# SparkFun_6DoF_ISM330DHCX_Qwiic_Micro.net
KiCad netlist of a schematic drawn in EAGLE
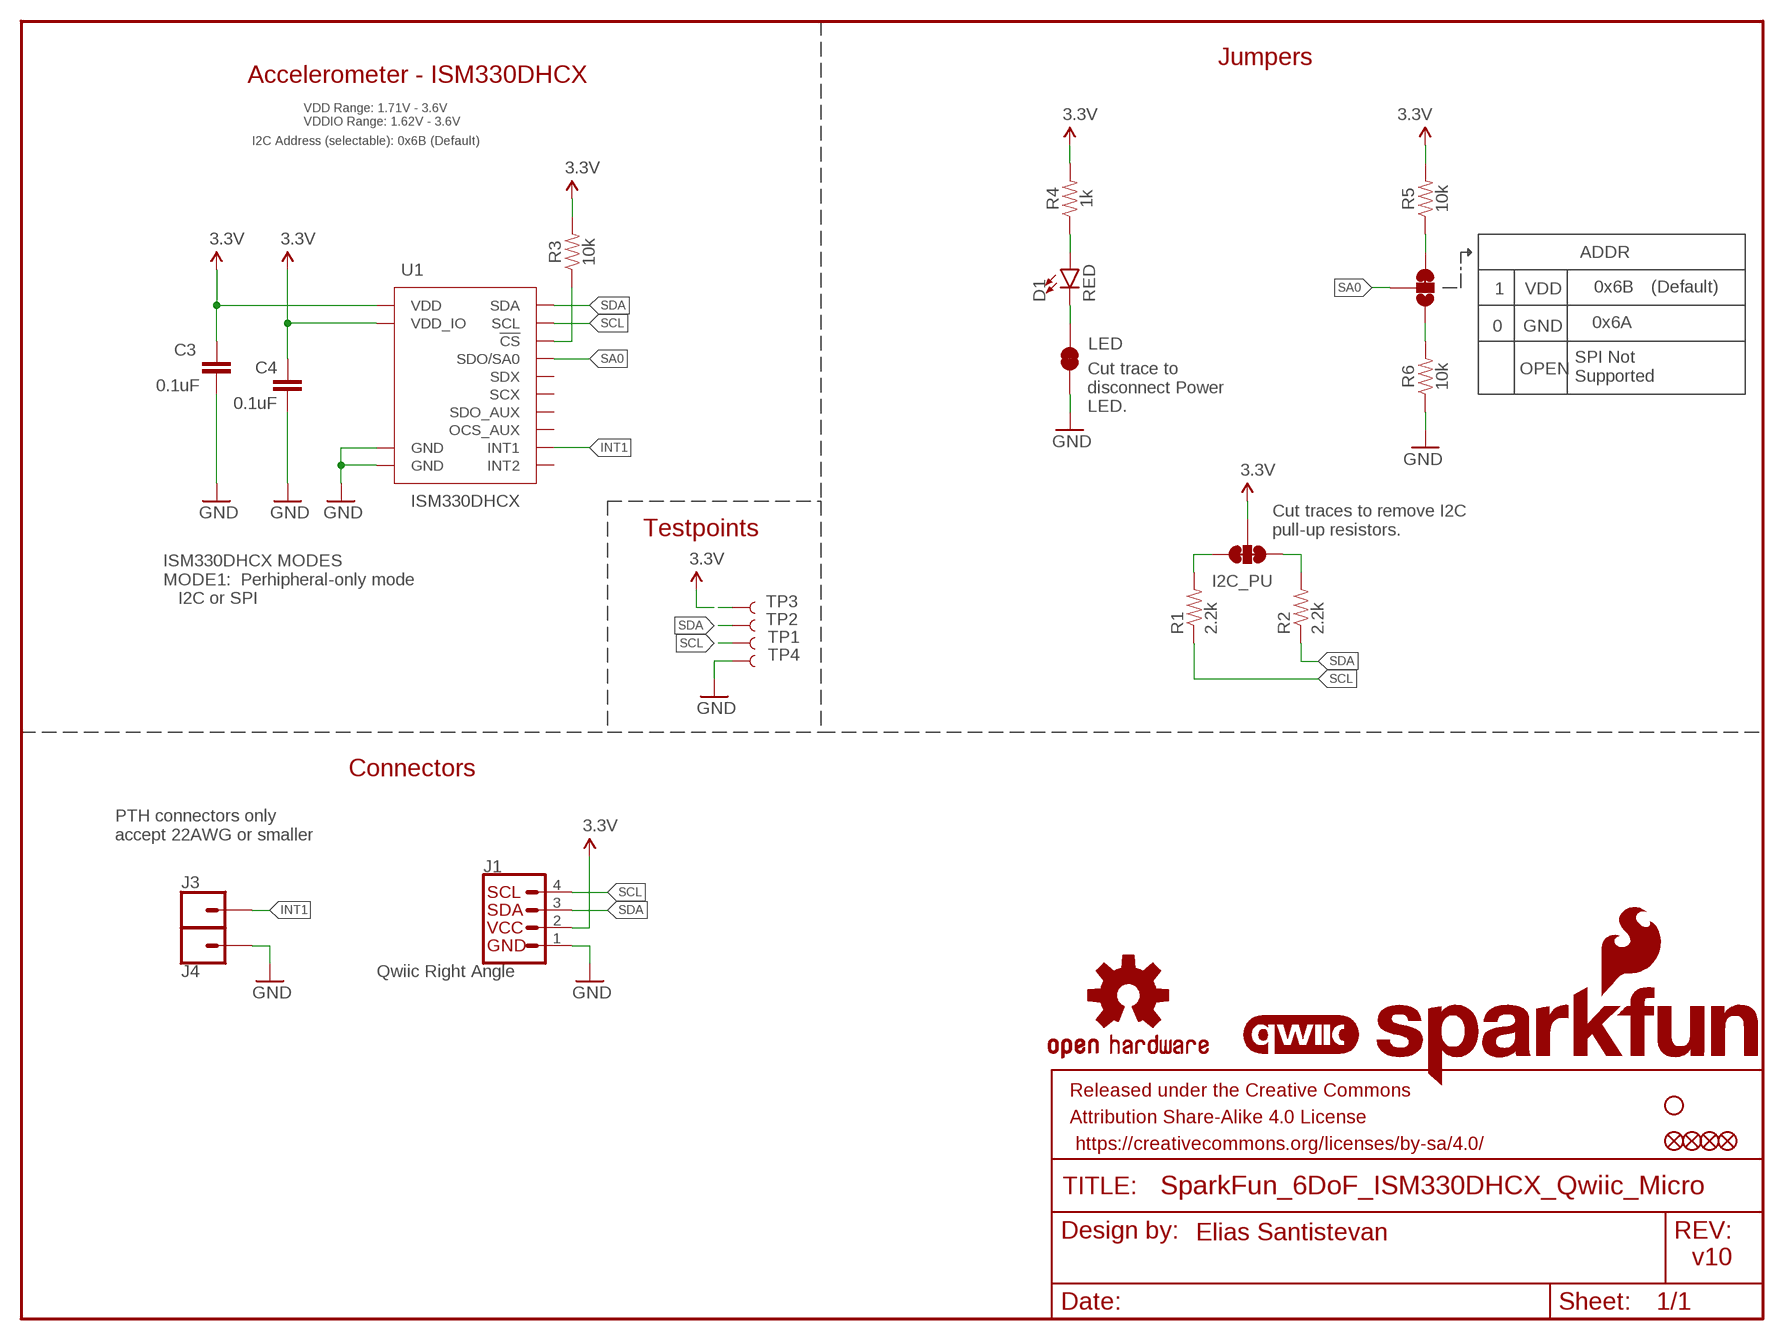
[diagram p0: schematic, sheet 1]

(export (version "E")
  (design (tool "Eeschema 10.0.6"))
  (components
    (comp (ref "ADDR")
      (value "JUMPER-SMT_3_1-NC_TRACE_SILK")
      (footprint "eagle-import:SMT-JUMPER_3_1-NC_TRACE_SILK")
      (libsource (lib "eagle-import") (part "JUMPER-SMT_3_1-NC_TRACE_SILK"))
    )
    (comp (ref "C3")
      (value "0.1uF")
      (footprint "eagle-import:0402-TIGHT")
      (libsource (lib "eagle-import") (part "0.1UF-0402T-6.3V-10%-X7R"))
    )
    (comp (ref "C4")
      (value "0.1uF")
      (footprint "eagle-import:0402-TIGHT")
      (libsource (lib "eagle-import") (part "0.1UF-0402T-6.3V-10%-X7R"))
    )
    (comp (ref "D1")
      (value "RED")
      (footprint "eagle-import:LED-0402")
      (libsource (lib "eagle-import") (part "LED-RED_0402"))
    )
    (comp (ref "FD1")
      (value "FIDUCIALUFIDUCIAL")
      (footprint "eagle-import:FIDUCIAL-MICRO")
      (libsource (lib "eagle-import") (part "FIDUCIALUFIDUCIAL"))
    )
    (comp (ref "FD2")
      (value "FIDUCIALUFIDUCIAL")
      (footprint "eagle-import:FIDUCIAL-MICRO")
      (libsource (lib "eagle-import") (part "FIDUCIALUFIDUCIAL"))
    )
    (comp (ref "FID1")
      (value "FIDUCIALUFIDUCIAL")
      (footprint "eagle-import:FIDUCIAL-MICRO")
      (libsource (lib "eagle-import") (part "FIDUCIALUFIDUCIAL"))
    )
    (comp (ref "FID2")
      (value "FIDUCIALUFIDUCIAL")
      (footprint "eagle-import:FIDUCIAL-MICRO")
      (libsource (lib "eagle-import") (part "FIDUCIALUFIDUCIAL"))
    )
    (comp (ref "FRAME1")
      (value "FRAME-LETTER")
      (footprint "eagle-import:CREATIVE_COMMONS")
      (fields (field (name "DESIGNER") "Elias Santistevan"))
      (libsource (lib "eagle-import") (part "FRAME-LETTER"))
    )
    (comp (ref "I2C_PU")
      (value "S_MODE")
      (footprint "eagle-import:SMT-JUMPER_3_2-NC_TRACE_SILK")
      (libsource (lib "eagle-import") (part "JUMPER-SMT_3_2-NC_TRACE_SILK"))
    )
    (comp (ref "J1")
      (value "Qwiic Right Angle")
      (footprint "eagle-import:JST04_1MM_RA")
      (libsource (lib "eagle-import") (part "I2C_STANDARDQWIIC"))
    )
    (comp (ref "J3")
      (value "CONN_01_1MM")
      (footprint "eagle-import:1X01_1MM_NO_SILK")
      (libsource (lib "eagle-import") (part "CONN_01_1MM"))
    )
    (comp (ref "J4")
      (value "CONN_01_1MM")
      (footprint "eagle-import:1X01_1MM_NO_SILK")
      (libsource (lib "eagle-import") (part "CONN_01_1MM"))
    )
    (comp (ref "LED")
      (value "JUMPER-SMT_2_NC_TRACE_SILK")
      (footprint "eagle-import:SMT-JUMPER_2_NC_TRACE_SILK")
      (libsource (lib "eagle-import") (part "JUMPER-SMT_2_NC_TRACE_SILK"))
    )
    (comp (ref "LOGO1")
      (value "QWIIC_LOGO_3MM")
      (footprint "eagle-import:QWIIC_3MM")
      (libsource (lib "eagle-import") (part "QWIIC_LOGO_3MM"))
    )
    (comp (ref "LOGO2")
      (value "OSHW-LOGOMINI")
      (footprint "eagle-import:OSHW-LOGO-MINI")
      (libsource (lib "eagle-import") (part "OSHW-LOGOMINI"))
    )
    (comp (ref "LOGO3")
      (value "SFE_LOGO_NAME_FLAMEBLANK")
      (footprint "eagle-import:BLANK")
      (libsource (lib "eagle-import") (part "SFE_LOGO_NAME_FLAMEBLANK"))
    )
    (comp (ref "R1")
      (value "2.2k")
      (footprint "eagle-import:0402-TIGHT")
      (libsource (lib "eagle-import") (part "2.2KOHM-0402T-1/16W-1%"))
    )
    (comp (ref "R2")
      (value "2.2k")
      (footprint "eagle-import:0402-TIGHT")
      (libsource (lib "eagle-import") (part "2.2KOHM-0402T-1/16W-1%"))
    )
    (comp (ref "R3")
      (value "10k")
      (footprint "eagle-import:0402-TIGHT")
      (libsource (lib "eagle-import") (part "10KOHM-0402T-1/16W-1%"))
    )
    (comp (ref "R4")
      (value "1k")
      (footprint "eagle-import:0402-TIGHT")
      (libsource (lib "eagle-import") (part "1KOHM-0402T-1/16W-1%"))
    )
    (comp (ref "R5")
      (value "10k")
      (footprint "eagle-import:0402-TIGHT")
      (libsource (lib "eagle-import") (part "10KOHM-0402T-1/16W-1%"))
    )
    (comp (ref "R6")
      (value "10k")
      (footprint "eagle-import:0402-TIGHT")
      (libsource (lib "eagle-import") (part "10KOHM-0402T-1/16W-1%"))
    )
    (comp (ref "STANDOFF1")
      (value "STAND-OFFTIGHT")
      (footprint "eagle-import:STAND-OFF-TIGHT")
      (libsource (lib "eagle-import") (part "STAND-OFFTIGHT"))
    )
    (comp (ref "TP1")
      (value "TEST-POINT3")
      (footprint "eagle-import:PAD.03X.03")
      (libsource (lib "eagle-import") (part "TEST-POINT3"))
    )
    (comp (ref "TP2")
      (value "TEST-POINT3")
      (footprint "eagle-import:PAD.03X.03")
      (libsource (lib "eagle-import") (part "TEST-POINT3"))
    )
    (comp (ref "TP3")
      (value "TEST-POINT3")
      (footprint "eagle-import:PAD.03X.03")
      (libsource (lib "eagle-import") (part "TEST-POINT3"))
    )
    (comp (ref "TP4")
      (value "TEST-POINT3")
      (footprint "eagle-import:PAD.03X.03")
      (libsource (lib "eagle-import") (part "TEST-POINT3"))
    )
    (comp (ref "U1")
      (value "ISM330DHCX")
      (footprint "eagle-import:LGA-14L")
      (libsource (lib "eagle-import") (part "ISM330DHCX"))
    )
  )
  (nets
    (net (code "1") (name "3.3V") (class "Default")
      (node (ref "C3") (pin "1") (pinfunction "1_1") (pintype "passive"))
      (node (ref "C4") (pin "1") (pinfunction "1_1") (pintype "passive"))
      (node (ref "I2C_PU") (pin "2") (pinfunction "2_2") (pintype "passive"))
      (node (ref "J1") (pin "2") (pinfunction "2_2") (pintype "power_in"))
      (node (ref "R3") (pin "2") (pinfunction "2_2") (pintype "passive"))
      (node (ref "R4") (pin "2") (pinfunction "2_2") (pintype "passive"))
      (node (ref "R5") (pin "2") (pinfunction "2_2") (pintype "passive"))
      (node (ref "TP3") (pin "1") (pinfunction "1_1") (pintype "bidirectional"))
      (node (ref "U1") (pin "P5") (pinfunction "VDD_IO_P5") (pintype "power_in"))
      (node (ref "U1") (pin "P8") (pinfunction "VDD_P8") (pintype "power_in"))
    )
    (net (code "2") (name "GND") (class "Default")
      (node (ref "C3") (pin "2") (pinfunction "2_2") (pintype "passive"))
      (node (ref "C4") (pin "2") (pinfunction "2_2") (pintype "passive"))
      (node (ref "J1") (pin "1") (pinfunction "1_1") (pintype "power_in"))
      (node (ref "J4") (pin "1") (pinfunction "1_1") (pintype "passive"))
      (node (ref "LED") (pin "1") (pinfunction "1_1") (pintype "passive"))
      (node (ref "R6") (pin "1") (pinfunction "1_1") (pintype "passive"))
      (node (ref "TP4") (pin "1") (pinfunction "1_1") (pintype "bidirectional"))
      (node (ref "U1") (pin "P6") (pinfunction "GND_P6") (pintype "power_in"))
      (node (ref "U1") (pin "P7") (pinfunction "GND_P7") (pintype "power_in"))
    )
    (net (code "3") (name "INT1") (class "Default")
      (node (ref "J3") (pin "1") (pinfunction "1_1") (pintype "passive"))
      (node (ref "U1") (pin "P4") (pinfunction "INT1_P4") (pintype "bidirectional"))
    )
    (net (code "4") (name "Net-(ADDR-Pad1)") (class "Default")
      (node (ref "ADDR") (pin "1") (pinfunction "1_1") (pintype "passive"))
      (node (ref "R6") (pin "2") (pinfunction "2_2") (pintype "passive"))
    )
    (net (code "5") (name "Net-(ADDR-Pad3)") (class "Default")
      (node (ref "ADDR") (pin "3") (pinfunction "3_3") (pintype "passive"))
      (node (ref "R5") (pin "1") (pinfunction "1_1") (pintype "passive"))
    )
    (net (code "6") (name "Net-(D1-PadA)") (class "Default")
      (node (ref "D1") (pin "A") (pinfunction "A_A") (pintype "passive"))
      (node (ref "R4") (pin "1") (pinfunction "1_1") (pintype "passive"))
    )
    (net (code "7") (name "Net-(D1-PadC)") (class "Default")
      (node (ref "D1") (pin "C") (pinfunction "C_C") (pintype "passive"))
      (node (ref "LED") (pin "2") (pinfunction "2_2") (pintype "passive"))
    )
    (net (code "8") (name "Net-(I2C_PU-Pad1)") (class "Default")
      (node (ref "I2C_PU") (pin "1") (pinfunction "1_1") (pintype "passive"))
      (node (ref "R1") (pin "2") (pinfunction "2_2") (pintype "passive"))
    )
    (net (code "9") (name "Net-(I2C_PU-Pad3)") (class "Default")
      (node (ref "I2C_PU") (pin "3") (pinfunction "3_3") (pintype "passive"))
      (node (ref "R2") (pin "2") (pinfunction "2_2") (pintype "passive"))
    )
    (net (code "10") (name "Net-(U1-~{CS})") (class "Default")
      (node (ref "R3") (pin "1") (pinfunction "1_1") (pintype "passive"))
      (node (ref "U1") (pin "P12") (pinfunction "~{CS}_P12") (pintype "bidirectional"))
    )
    (net (code "11") (name "SA0") (class "Default")
      (node (ref "ADDR") (pin "2") (pinfunction "2_2") (pintype "passive"))
      (node (ref "U1") (pin "P1") (pinfunction "SDO/SA0_P1") (pintype "bidirectional"))
    )
    (net (code "12") (name "SCL") (class "Default")
      (node (ref "J1") (pin "4") (pinfunction "4_4") (pintype "passive"))
      (node (ref "R1") (pin "1") (pinfunction "1_1") (pintype "passive"))
      (node (ref "TP1") (pin "1") (pinfunction "1_1") (pintype "bidirectional"))
      (node (ref "U1") (pin "P13") (pinfunction "SCL_P13") (pintype "bidirectional"))
    )
    (net (code "13") (name "SDA") (class "Default")
      (node (ref "J1") (pin "3") (pinfunction "3_3") (pintype "passive"))
      (node (ref "R2") (pin "1") (pinfunction "1_1") (pintype "passive"))
      (node (ref "TP2") (pin "1") (pinfunction "1_1") (pintype "bidirectional"))
      (node (ref "U1") (pin "P14") (pinfunction "SDA_P14") (pintype "bidirectional"))
    )
    (net (code "14") (name "unconnected-(U1-INT2-PadP9)") (class "Default")
      (node (ref "U1") (pin "P9") (pinfunction "INT2_P9") (pintype "bidirectional"))
    )
    (net (code "15") (name "unconnected-(U1-OCS_AUX-PadP10)") (class "Default")
      (node (ref "U1") (pin "P10") (pinfunction "OCS_AUX_P10") (pintype "bidirectional"))
    )
    (net (code "16") (name "unconnected-(U1-SCX-PadP3)") (class "Default")
      (node (ref "U1") (pin "P3") (pinfunction "SCX_P3") (pintype "bidirectional"))
    )
    (net (code "17") (name "unconnected-(U1-SDO_AUX-PadP11)") (class "Default")
      (node (ref "U1") (pin "P11") (pinfunction "SDO_AUX_P11") (pintype "bidirectional"))
    )
    (net (code "18") (name "unconnected-(U1-SDX-PadP2)") (class "Default")
      (node (ref "U1") (pin "P2") (pinfunction "SDX_P2") (pintype "bidirectional"))
    )
  )
)
